# dcmctrl-mcu-board_v1.net
KiCad netlist of a schematic drawn in EAGLE
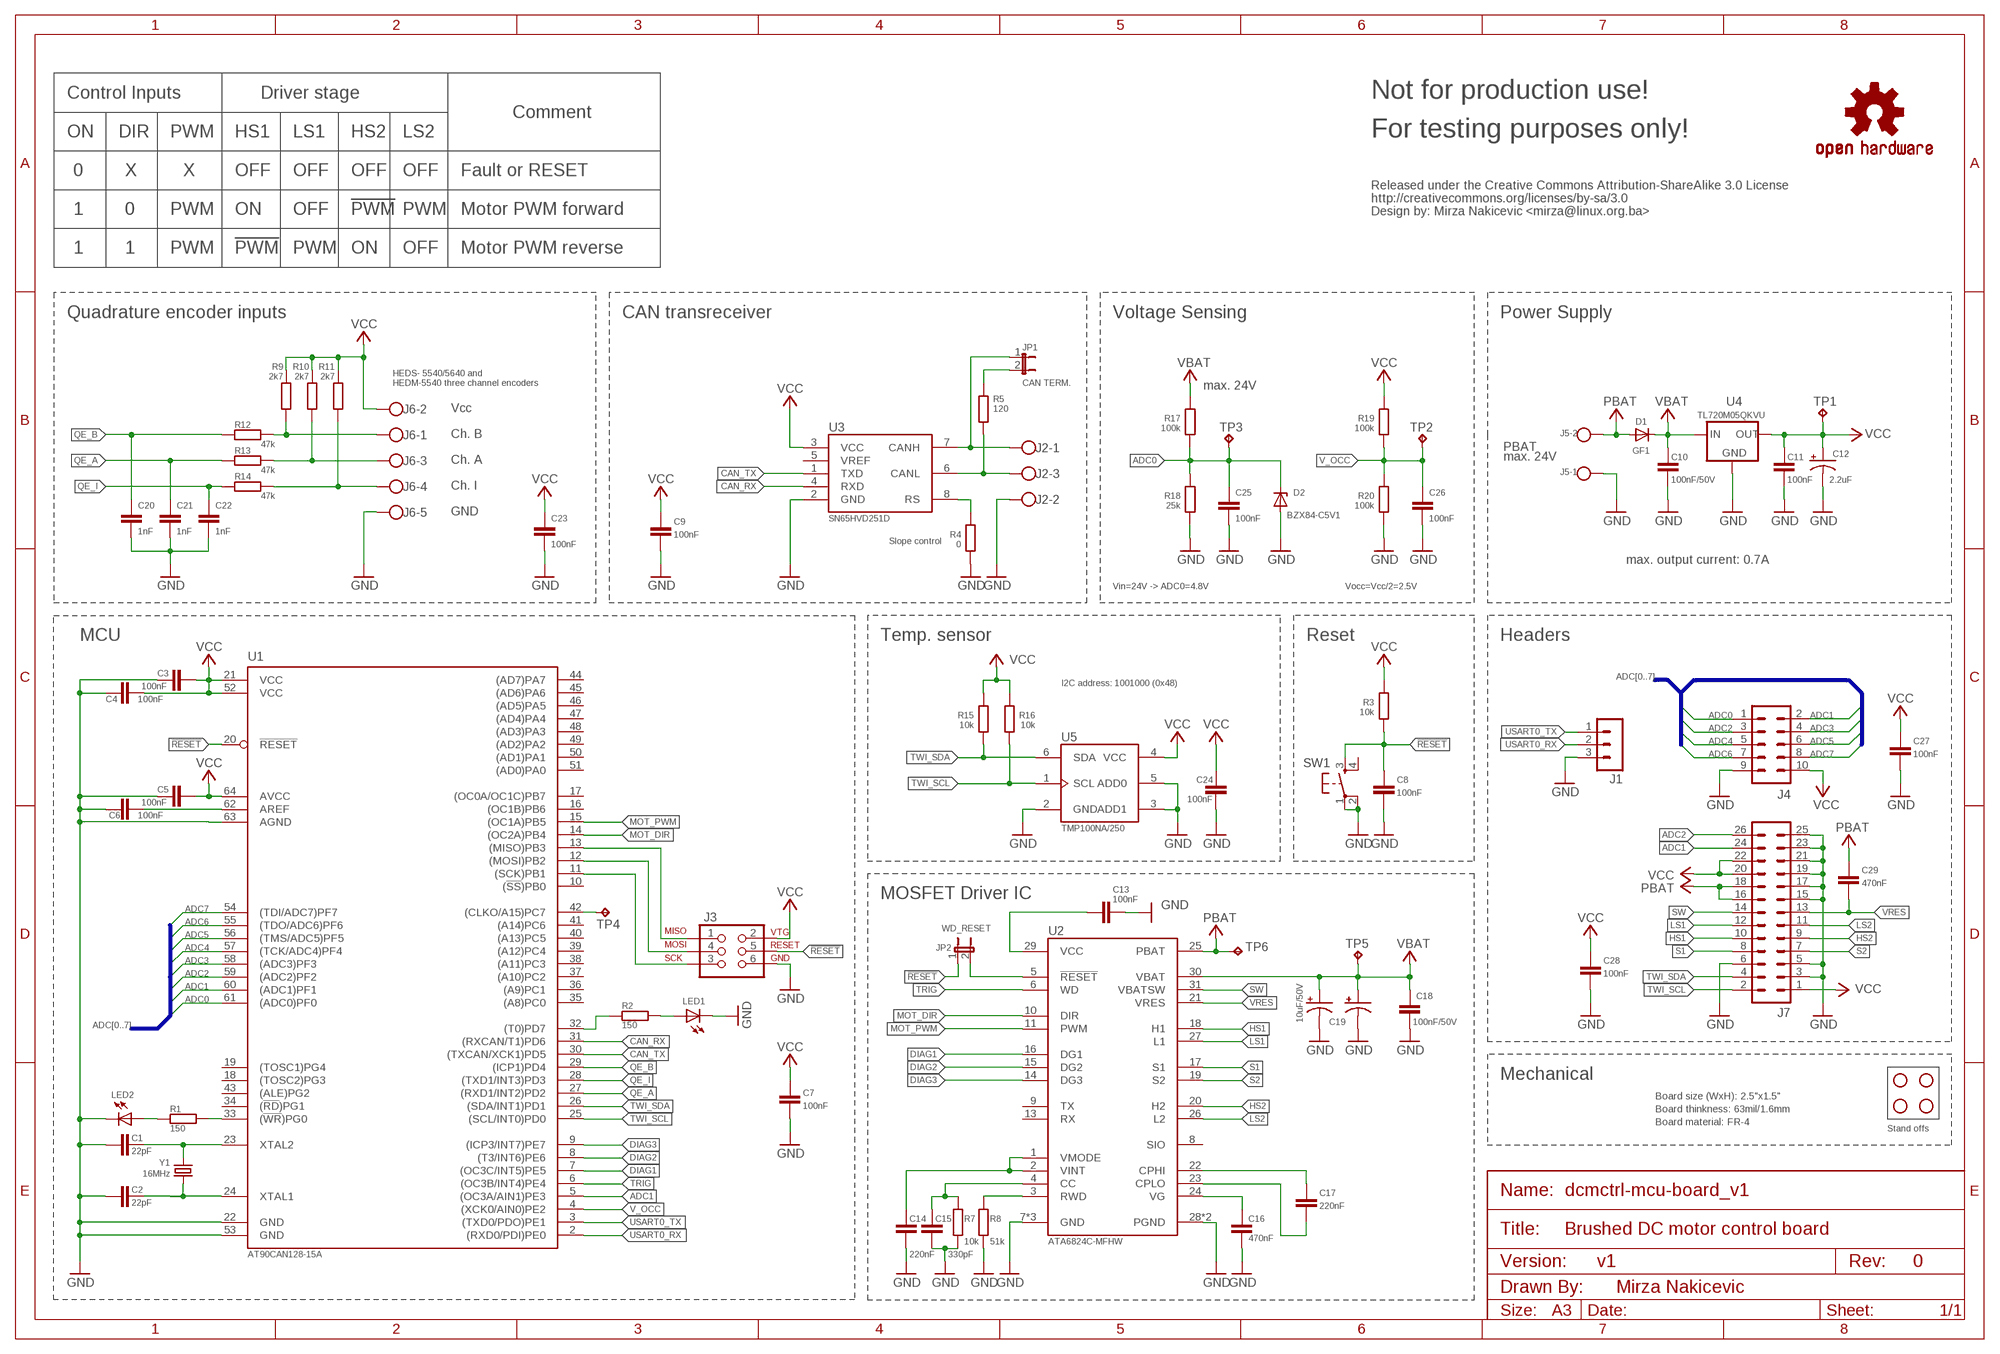
[diagram p0: schematic, sheet 1]

(export (version "E")
  (design (tool "Eeschema 10.0.6"))
  (components
    (comp (ref "C1")
      (value "22pF")
      (footprint "eagle-import:C0603")
      (libsource (lib "eagle-import") (part "C-0603"))
    )
    (comp (ref "C2")
      (value "22pF")
      (footprint "eagle-import:C0603")
      (libsource (lib "eagle-import") (part "C-0603"))
    )
    (comp (ref "C3")
      (value "100nF")
      (footprint "eagle-import:C0603")
      (libsource (lib "eagle-import") (part "C-0603"))
    )
    (comp (ref "C4")
      (value "100nF")
      (footprint "eagle-import:C0603")
      (libsource (lib "eagle-import") (part "C-0603"))
    )
    (comp (ref "C5")
      (value "100nF")
      (footprint "eagle-import:C0603")
      (libsource (lib "eagle-import") (part "C-0603"))
    )
    (comp (ref "C6")
      (value "100nF")
      (footprint "eagle-import:C0603")
      (libsource (lib "eagle-import") (part "C-0603"))
    )
    (comp (ref "C7")
      (value "100nF")
      (footprint "eagle-import:C0603")
      (libsource (lib "eagle-import") (part "C-0603"))
    )
    (comp (ref "C8")
      (value "100nF")
      (footprint "eagle-import:C0603")
      (libsource (lib "eagle-import") (part "C-0603"))
    )
    (comp (ref "C9")
      (value "100nF")
      (footprint "eagle-import:C0603")
      (libsource (lib "eagle-import") (part "C-0603"))
    )
    (comp (ref "C10")
      (value "100nF/50V")
      (footprint "eagle-import:C0603")
      (libsource (lib "eagle-import") (part "C-0603"))
    )
    (comp (ref "C11")
      (value "100nF")
      (footprint "eagle-import:C0603")
      (libsource (lib "eagle-import") (part "C-0603"))
    )
    (comp (ref "C12")
      (value "2.2uF")
      (footprint "eagle-import:EIA3216")
      (libsource (lib "eagle-import") (part "CPOL-1206"))
    )
    (comp (ref "C13")
      (value "100nF")
      (footprint "eagle-import:C0603")
      (libsource (lib "eagle-import") (part "C-0603"))
    )
    (comp (ref "C14")
      (value "220nF")
      (footprint "eagle-import:C0603")
      (libsource (lib "eagle-import") (part "C-0603"))
    )
    (comp (ref "C15")
      (value "330pF")
      (footprint "eagle-import:C0603")
      (libsource (lib "eagle-import") (part "C-0603"))
    )
    (comp (ref "C16")
      (value "470nF")
      (footprint "eagle-import:C0603")
      (libsource (lib "eagle-import") (part "C-0603"))
    )
    (comp (ref "C17")
      (value "220nF")
      (footprint "eagle-import:C0603")
      (libsource (lib "eagle-import") (part "C-0603"))
    )
    (comp (ref "C18")
      (value "100nF/50V")
      (footprint "eagle-import:C0603")
      (libsource (lib "eagle-import") (part "C-0603"))
    )
    (comp (ref "C19")
      (value "10uF/50V")
      (footprint "eagle-import:EIA3528")
      (libsource (lib "eagle-import") (part "CPOL-3528"))
    )
    (comp (ref "C20")
      (value "1nF")
      (footprint "eagle-import:C0603")
      (libsource (lib "eagle-import") (part "C-0603"))
    )
    (comp (ref "C21")
      (value "1nF")
      (footprint "eagle-import:C0603")
      (libsource (lib "eagle-import") (part "C-0603"))
    )
    (comp (ref "C22")
      (value "1nF")
      (footprint "eagle-import:C0603")
      (libsource (lib "eagle-import") (part "C-0603"))
    )
    (comp (ref "C23")
      (value "100nF")
      (footprint "eagle-import:C0603")
      (libsource (lib "eagle-import") (part "C-0603"))
    )
    (comp (ref "C24")
      (value "100nF")
      (footprint "eagle-import:C0603")
      (libsource (lib "eagle-import") (part "C-0603"))
    )
    (comp (ref "C25")
      (value "100nF")
      (footprint "eagle-import:C0603")
      (libsource (lib "eagle-import") (part "C-0603"))
    )
    (comp (ref "C26")
      (value "100nF")
      (footprint "eagle-import:C0603")
      (libsource (lib "eagle-import") (part "C-0603"))
    )
    (comp (ref "C27")
      (value "100nF")
      (footprint "eagle-import:C0603")
      (libsource (lib "eagle-import") (part "C-0603"))
    )
    (comp (ref "C28")
      (value "100nF")
      (footprint "eagle-import:C0603")
      (libsource (lib "eagle-import") (part "C-0603"))
    )
    (comp (ref "C29")
      (value "470nF")
      (footprint "eagle-import:C0603")
      (libsource (lib "eagle-import") (part "C-0603"))
    )
    (comp (ref "C999")
      (value "10uF/50V")
      (footprint "eagle-import:RADIAL-1")
      (libsource (lib "eagle-import") (part "CPOL-PTH-2"))
    )
    (comp (ref "D1")
      (value "GF1")
      (footprint "eagle-import:SMA-DO214AC")
      (libsource (lib "eagle-import") (part "GF1"))
    )
    (comp (ref "D2")
      (value "BZX84-C5V1")
      (footprint "eagle-import:TO236")
      (libsource (lib "eagle-import") (part "ZENER-DIODETO236"))
    )
    (comp (ref "J1")
      (value "MA03-1")
      (footprint "eagle-import:MA03-1")
      (libsource (lib "eagle-import") (part "MA03-1"))
    )
    (comp (ref "J2")
      (value "BLOCK3-3.5-4UCON")
      (footprint "eagle-import:4UCON-20193")
      (libsource (lib "eagle-import") (part "BLOCK3-3.5-4UCON"))
    )
    (comp (ref "J3")
      (value "AVR-ISP-6-100")
      (footprint "eagle-import:2X3-100")
      (libsource (lib "eagle-import") (part "AVR-ISP-6-100"))
    )
    (comp (ref "J4")
      (value "MA05-2")
      (footprint "eagle-import:MA05-2")
      (libsource (lib "eagle-import") (part "MA05-2"))
    )
    (comp (ref "J5")
      (value "BLOCK2-3.5-4UCON")
      (footprint "eagle-import:4UCON-19963")
      (libsource (lib "eagle-import") (part "BLOCK2-3.5-4UCON"))
    )
    (comp (ref "J6")
      (value "BLOCK5-3.5-4UCON")
      (footprint "eagle-import:4UCON-20223")
      (libsource (lib "eagle-import") (part "BLOCK5-3.5-4UCON"))
    )
    (comp (ref "J7")
      (value "MA13-2")
      (footprint "eagle-import:MA13-2")
      (libsource (lib "eagle-import") (part "MA13-2"))
    )
    (comp (ref "JP1")
      (value "JUMPER-2PTH")
      (footprint "eagle-import:1X02")
      (libsource (lib "eagle-import") (part "JUMPER-2PTH"))
    )
    (comp (ref "JP2")
      (value "JUMPER-2SMD-NC")
      (footprint "eagle-import:SJ_2S")
      (libsource (lib "eagle-import") (part "JUMPER-2SMD-NC"))
    )
    (comp (ref "LED1")
      (value "LEDCHIPLED_0603")
      (footprint "eagle-import:CHIPLED_0603")
      (libsource (lib "eagle-import") (part "LEDCHIPLED_0603"))
    )
    (comp (ref "LED2")
      (value "LEDCHIPLED_0603")
      (footprint "eagle-import:CHIPLED_0603")
      (libsource (lib "eagle-import") (part "LEDCHIPLED_0603"))
    )
    (comp (ref "R1")
      (value "150")
      (footprint "eagle-import:R0603")
      (libsource (lib "eagle-import") (part "R-0603"))
    )
    (comp (ref "R2")
      (value "150")
      (footprint "eagle-import:R0603")
      (libsource (lib "eagle-import") (part "R-0603"))
    )
    (comp (ref "R3")
      (value "10k")
      (footprint "eagle-import:R0603")
      (libsource (lib "eagle-import") (part "R-0603"))
    )
    (comp (ref "R4")
      (value "0")
      (footprint "eagle-import:R0603")
      (libsource (lib "eagle-import") (part "R-0603"))
    )
    (comp (ref "R5")
      (value "120")
      (footprint "eagle-import:R0805")
      (libsource (lib "eagle-import") (part "R-0805"))
    )
    (comp (ref "R7")
      (value "10k")
      (footprint "eagle-import:R0603")
      (libsource (lib "eagle-import") (part "R-0603"))
    )
    (comp (ref "R8")
      (value "51k")
      (footprint "eagle-import:R0603")
      (libsource (lib "eagle-import") (part "R-0603"))
    )
    (comp (ref "R9")
      (value "2k7")
      (footprint "eagle-import:R0603")
      (libsource (lib "eagle-import") (part "R-0603"))
    )
    (comp (ref "R10")
      (value "2k7")
      (footprint "eagle-import:R0603")
      (libsource (lib "eagle-import") (part "R-0603"))
    )
    (comp (ref "R11")
      (value "2k7")
      (footprint "eagle-import:R0603")
      (libsource (lib "eagle-import") (part "R-0603"))
    )
    (comp (ref "R12")
      (value "47k")
      (footprint "eagle-import:R0603")
      (libsource (lib "eagle-import") (part "R-0603"))
    )
    (comp (ref "R13")
      (value "47k")
      (footprint "eagle-import:R0603")
      (libsource (lib "eagle-import") (part "R-0603"))
    )
    (comp (ref "R14")
      (value "47k")
      (footprint "eagle-import:R0603")
      (libsource (lib "eagle-import") (part "R-0603"))
    )
    (comp (ref "R15")
      (value "10k")
      (footprint "eagle-import:R0603")
      (libsource (lib "eagle-import") (part "R-0603"))
    )
    (comp (ref "R16")
      (value "10k")
      (footprint "eagle-import:R0603")
      (libsource (lib "eagle-import") (part "R-0603"))
    )
    (comp (ref "R17")
      (value "100k")
      (footprint "eagle-import:R0603")
      (libsource (lib "eagle-import") (part "R-0603"))
    )
    (comp (ref "R18")
      (value "25k")
      (footprint "eagle-import:R0603")
      (libsource (lib "eagle-import") (part "R-0603"))
    )
    (comp (ref "R19")
      (value "100k")
      (footprint "eagle-import:R0603")
      (libsource (lib "eagle-import") (part "R-0603"))
    )
    (comp (ref "R20")
      (value "100k")
      (footprint "eagle-import:R0603")
      (libsource (lib "eagle-import") (part "R-0603"))
    )
    (comp (ref "SW1")
      (value "TAC_SWITCHPTH")
      (footprint "eagle-import:TACTILE-PTH")
      (libsource (lib "eagle-import") (part "TAC_SWITCHPTH"))
    )
    (comp (ref "TP1")
      (value "TPB1,27")
      (footprint "eagle-import:B1,27")
      (libsource (lib "eagle-import") (part "TPB1,27"))
    )
    (comp (ref "TP2")
      (value "TPB1,27")
      (footprint "eagle-import:B1,27")
      (libsource (lib "eagle-import") (part "TPB1,27"))
    )
    (comp (ref "TP3")
      (value "TPB1,27")
      (footprint "eagle-import:B1,27")
      (libsource (lib "eagle-import") (part "TPB1,27"))
    )
    (comp (ref "TP4")
      (value "TPB1,27")
      (footprint "eagle-import:B1,27")
      (libsource (lib "eagle-import") (part "TPB1,27"))
    )
    (comp (ref "TP5")
      (value "TPB1,27")
      (footprint "eagle-import:B1,27")
      (libsource (lib "eagle-import") (part "TPB1,27"))
    )
    (comp (ref "TP6")
      (value "TPB1,27")
      (footprint "eagle-import:B1,27")
      (libsource (lib "eagle-import") (part "TPB1,27"))
    )
    (comp (ref "U$1")
      (value "STAND-OFF")
      (footprint "eagle-import:STAND-OFF")
      (libsource (lib "eagle-import") (part "STAND-OFF"))
    )
    (comp (ref "U$2")
      (value "STAND-OFF")
      (footprint "eagle-import:STAND-OFF")
      (libsource (lib "eagle-import") (part "STAND-OFF"))
    )
    (comp (ref "U$3")
      (value "STAND-OFF")
      (footprint "eagle-import:STAND-OFF")
      (libsource (lib "eagle-import") (part "STAND-OFF"))
    )
    (comp (ref "U$4")
      (value "STAND-OFF")
      (footprint "eagle-import:STAND-OFF")
      (libsource (lib "eagle-import") (part "STAND-OFF"))
    )
    (comp (ref "U$24")
      (value "OSHW-LOGOM")
      (footprint "eagle-import:OSHW-LOGO-M")
      (libsource (lib "eagle-import") (part "OSHW-LOGOM"))
    )
    (comp (ref "U$29")
      (value "CC-SA")
      (footprint "eagle-import:CC-SA")
      (libsource (lib "eagle-import") (part "CC-SA"))
    )
    (comp (ref "U1")
      (value "AT90CAN128-15A")
      (footprint "eagle-import:TQFP64")
      (libsource (lib "eagle-import") (part "AT90CAN-15A128"))
    )
    (comp (ref "U2")
      (value "ATA6824C-MFHW")
      (footprint "eagle-import:TPQFP32")
      (libsource (lib "eagle-import") (part "ATA6824C-MFHW"))
    )
    (comp (ref "U3")
      (value "SN65HVD251D")
      (footprint "eagle-import:SO-08")
      (libsource (lib "eagle-import") (part "SN65HVD251D"))
    )
    (comp (ref "U4")
      (value "TL720M05QKVU")
      (footprint "eagle-import:D-PAK_TO252AA")
      (libsource (lib "eagle-import") (part "TL720M05QKVU"))
    )
    (comp (ref "U5")
      (value "TMP100NA/250")
      (footprint "eagle-import:SOT23-6L")
      (libsource (lib "eagle-import") (part "TMP100NA/250"))
    )
    (comp (ref "Y1")
      (value "16MHz")
      (footprint "eagle-import:HC49U-V")
      (libsource (lib "eagle-import") (part "CRYSTAL-HC49UV"))
    )
  )
  (nets
    (net (code "1") (name "/ADC3") (class "Default")
      (node (ref "J4") (pin "4") (pinfunction "4_4") (pintype "passive"))
      (node (ref "U1") (pin "58") (pinfunction "(ADC3)PF3_58") (pintype "bidirectional"))
    )
    (net (code "2") (name "/ADC4") (class "Default")
      (node (ref "J4") (pin "5") (pinfunction "5_5") (pintype "passive"))
      (node (ref "U1") (pin "57") (pinfunction "(TCK/ADC4)PF4_57") (pintype "bidirectional"))
    )
    (net (code "3") (name "/ADC5") (class "Default")
      (node (ref "J4") (pin "6") (pinfunction "6_6") (pintype "passive"))
      (node (ref "U1") (pin "56") (pinfunction "(TMS/ADC5)PF5_56") (pintype "bidirectional"))
    )
    (net (code "4") (name "/ADC6") (class "Default")
      (node (ref "J4") (pin "7") (pinfunction "7_7") (pintype "passive"))
      (node (ref "U1") (pin "55") (pinfunction "(TDO/ADC6)PF6_55") (pintype "bidirectional"))
    )
    (net (code "5") (name "/ADC7") (class "Default")
      (node (ref "J4") (pin "8") (pinfunction "8_8") (pintype "passive"))
      (node (ref "U1") (pin "54") (pinfunction "(TDI/ADC7)PF7_54") (pintype "bidirectional"))
    )
    (net (code "7") (name "/~{RESET}") (class "Default")
      (node (ref "C8") (pin "1") (pinfunction "1_1") (pintype "passive"))
      (node (ref "J3") (pin "5") (pinfunction "5_5") (pintype "passive"))
      (node (ref "JP2") (pin "1") (pinfunction "1_1") (pintype "passive"))
      (node (ref "R3") (pin "1") (pinfunction "1_1") (pintype "passive"))
      (node (ref "SW1") (pin "3") (pinfunction "3_3") (pintype "passive"))
      (node (ref "U1") (pin "20") (pinfunction "~{RESET}_20") (pintype "input"))
    )
    (net (code "8") (name "ADC0") (class "Default")
      (node (ref "C25") (pin "1") (pinfunction "1_1") (pintype "passive"))
      (node (ref "D2") (pin "C") (pinfunction "C_C") (pintype "passive"))
      (node (ref "J4") (pin "1") (pinfunction "1_1") (pintype "passive"))
      (node (ref "R17") (pin "1") (pinfunction "1_1") (pintype "passive"))
      (node (ref "R18") (pin "2") (pinfunction "2_2") (pintype "passive"))
      (node (ref "TP3") (pin "TP") (pinfunction "TP_TP") (pintype "input"))
      (node (ref "U1") (pin "61") (pinfunction "(ADC0)PF0_61") (pintype "bidirectional"))
    )
    (net (code "9") (name "ADC1") (class "Default")
      (node (ref "J4") (pin "2") (pinfunction "2_2") (pintype "passive"))
      (node (ref "J7") (pin "24") (pinfunction "24_24") (pintype "passive"))
      (node (ref "U1") (pin "5") (pinfunction "(OC3A/AIN1)PE3_5") (pintype "bidirectional"))
      (node (ref "U1") (pin "60") (pinfunction "(ADC1)PF1_60") (pintype "bidirectional"))
    )
    (net (code "10") (name "ADC2") (class "Default")
      (node (ref "J4") (pin "3") (pinfunction "3_3") (pintype "passive"))
      (node (ref "J7") (pin "26") (pinfunction "26_26") (pintype "passive"))
      (node (ref "U1") (pin "59") (pinfunction "(ADC2)PF2_59") (pintype "bidirectional"))
    )
    (net (code "11") (name "CAN_RX") (class "Default")
      (node (ref "U1") (pin "31") (pinfunction "(RXCAN/T1)PD6_31") (pintype "bidirectional"))
      (node (ref "U3") (pin "4") (pinfunction "RXD_4") (pintype "bidirectional"))
    )
    (net (code "12") (name "CAN_TX") (class "Default")
      (node (ref "U1") (pin "30") (pinfunction "(TXCAN/XCK1)PD5_30") (pintype "bidirectional"))
      (node (ref "U3") (pin "1") (pinfunction "TXD_1") (pintype "output"))
    )
    (net (code "13") (name "DIAG1") (class "Default")
      (node (ref "U1") (pin "7") (pinfunction "(OC3C/INT5)PE5_7") (pintype "bidirectional"))
      (node (ref "U2") (pin "16") (pinfunction "DG1_16") (pintype "output"))
    )
    (net (code "14") (name "DIAG2") (class "Default")
      (node (ref "U1") (pin "8") (pinfunction "(T3/INT6)PE6_8") (pintype "bidirectional"))
      (node (ref "U2") (pin "15") (pinfunction "DG2_15") (pintype "output"))
    )
    (net (code "15") (name "DIAG3") (class "Default")
      (node (ref "U1") (pin "9") (pinfunction "(ICP3/INT7)PE7_9") (pintype "bidirectional"))
      (node (ref "U2") (pin "14") (pinfunction "DG3_14") (pintype "output"))
    )
    (net (code "16") (name "GND") (class "Default")
      (node (ref "C1") (pin "2") (pinfunction "2_2") (pintype "passive"))
      (node (ref "C10") (pin "2") (pinfunction "2_2") (pintype "passive"))
      (node (ref "C11") (pin "2") (pinfunction "2_2") (pintype "passive"))
      (node (ref "C12") (pin "C") (pinfunction "-_C") (pintype "passive"))
      (node (ref "C13") (pin "2") (pinfunction "2_2") (pintype "passive"))
      (node (ref "C14") (pin "2") (pinfunction "2_2") (pintype "passive"))
      (node (ref "C15") (pin "2") (pinfunction "2_2") (pintype "passive"))
      (node (ref "C16") (pin "2") (pinfunction "2_2") (pintype "passive"))
      (node (ref "C18") (pin "2") (pinfunction "2_2") (pintype "passive"))
      (node (ref "C19") (pin "C") (pinfunction "-_C") (pintype "passive"))
      (node (ref "C2") (pin "2") (pinfunction "2_2") (pintype "passive"))
      (node (ref "C20") (pin "2") (pinfunction "2_2") (pintype "passive"))
      (node (ref "C21") (pin "2") (pinfunction "2_2") (pintype "passive"))
      (node (ref "C22") (pin "2") (pinfunction "2_2") (pintype "passive"))
      (node (ref "C23") (pin "2") (pinfunction "2_2") (pintype "passive"))
      (node (ref "C24") (pin "2") (pinfunction "2_2") (pintype "passive"))
      (node (ref "C25") (pin "2") (pinfunction "2_2") (pintype "passive"))
      (node (ref "C26") (pin "2") (pinfunction "2_2") (pintype "passive"))
      (node (ref "C27") (pin "2") (pinfunction "2_2") (pintype "passive"))
      (node (ref "C28") (pin "2") (pinfunction "2_2") (pintype "passive"))
      (node (ref "C3") (pin "2") (pinfunction "2_2") (pintype "passive"))
      (node (ref "C4") (pin "2") (pinfunction "2_2") (pintype "passive"))
      (node (ref "C5") (pin "2") (pinfunction "2_2") (pintype "passive"))
      (node (ref "C6") (pin "2") (pinfunction "2_2") (pintype "passive"))
      (node (ref "C7") (pin "2") (pinfunction "2_2") (pintype "passive"))
      (node (ref "C8") (pin "2") (pinfunction "2_2") (pintype "passive"))
      (node (ref "C9") (pin "2") (pinfunction "2_2") (pintype "passive"))
      (node (ref "C999") (pin "2") (pinfunction "-_2") (pintype "passive"))
      (node (ref "D2") (pin "A") (pinfunction "A_A") (pintype "passive"))
      (node (ref "J1") (pin "3") (pinfunction "3_3") (pintype "passive"))
      (node (ref "J2") (pin "2") (pinfunction "KL_2") (pintype "passive"))
      (node (ref "J3") (pin "6") (pinfunction "6_6") (pintype "passive"))
      (node (ref "J4") (pin "9") (pinfunction "9_9") (pintype "passive"))
      (node (ref "J5") (pin "1") (pinfunction "KL_1") (pintype "passive"))
      (node (ref "J6") (pin "5") (pinfunction "KL_5") (pintype "passive"))
      (node (ref "J7") (pin "15") (pinfunction "15_15") (pintype "passive"))
      (node (ref "J7") (pin "17") (pinfunction "17_17") (pintype "passive"))
      (node (ref "J7") (pin "19") (pinfunction "19_19") (pintype "passive"))
      (node (ref "J7") (pin "21") (pinfunction "21_21") (pintype "passive"))
      (node (ref "J7") (pin "23") (pinfunction "23_23") (pintype "passive"))
      (node (ref "J7") (pin "25") (pinfunction "25_25") (pintype "passive"))
      (node (ref "J7") (pin "3") (pinfunction "3_3") (pintype "passive"))
      (node (ref "J7") (pin "5") (pinfunction "5_5") (pintype "passive"))
      (node (ref "J7") (pin "6") (pinfunction "6_6") (pintype "passive"))
      (node (ref "LED1") (pin "C") (pinfunction "C_C") (pintype "passive"))
      (node (ref "LED2") (pin "C") (pinfunction "C_C") (pintype "passive"))
      (node (ref "R18") (pin "1") (pinfunction "1_1") (pintype "passive"))
      (node (ref "R20") (pin "1") (pinfunction "1_1") (pintype "passive"))
      (node (ref "R4") (pin "1") (pinfunction "1_1") (pintype "passive"))
      (node (ref "R7") (pin "1") (pinfunction "1_1") (pintype "passive"))
      (node (ref "R8") (pin "1") (pinfunction "1_1") (pintype "passive"))
      (node (ref "SW1") (pin "1") (pinfunction "1_1") (pintype "passive"))
      (node (ref "SW1") (pin "2") (pinfunction "2_2") (pintype "passive"))
      (node (ref "U1") (pin "22") (pinfunction "GND_22") (pintype "power_in"))
      (node (ref "U1") (pin "53") (pinfunction "GND_53") (pintype "power_in"))
      (node (ref "U1") (pin "63") (pinfunction "AGND_63") (pintype "power_in"))
      (node (ref "U2") (pin "12") (pinfunction "GND_12") (pintype "power_in"))
      (node (ref "U2") (pin "28") (pinfunction "PGND_28") (pintype "input"))
      (node (ref "U2") (pin "32") (pinfunction "GND_32") (pintype "power_in"))
      (node (ref "U2") (pin "33") (pinfunction "PGND_33") (pintype "input"))
      (node (ref "U2") (pin "7") (pinfunction "GND_7") (pintype "power_in"))
      (node (ref "U3") (pin "2") (pinfunction "GND_2") (pintype "power_in"))
      (node (ref "U4") (pin "4") (pinfunction "GND_4") (pintype "power_in"))
      (node (ref "U5") (pin "2") (pinfunction "GND_2") (pintype "power_in"))
      (node (ref "U5") (pin "3") (pinfunction "ADD1_3") (pintype "input"))
      (node (ref "U5") (pin "5") (pinfunction "ADD0_5") (pintype "input"))
    )
    (net (code "17") (name "HS1") (class "Default")
      (node (ref "J7") (pin "10") (pinfunction "10_10") (pintype "passive"))
      (node (ref "U2") (pin "18") (pinfunction "H1_18") (pintype "output"))
    )
    (net (code "18") (name "HS2") (class "Default")
      (node (ref "J7") (pin "9") (pinfunction "9_9") (pintype "passive"))
      (node (ref "U2") (pin "20") (pinfunction "H2_20") (pintype "output"))
    )
    (net (code "19") (name "LS1") (class "Default")
      (node (ref "J7") (pin "12") (pinfunction "12_12") (pintype "passive"))
      (node (ref "U2") (pin "27") (pinfunction "L1_27") (pintype "output"))
    )
    (net (code "20") (name "LS2") (class "Default")
      (node (ref "J7") (pin "11") (pinfunction "11_11") (pintype "passive"))
      (node (ref "U2") (pin "26") (pinfunction "L2_26") (pintype "output"))
    )
    (net (code "21") (name "MOT_DIR") (class "Default")
      (node (ref "U1") (pin "14") (pinfunction "(OC2A)PB4_14") (pintype "bidirectional"))
      (node (ref "U2") (pin "10") (pinfunction "DIR_10") (pintype "input"))
    )
    (net (code "22") (name "MOT_PWM") (class "Default")
      (node (ref "U1") (pin "15") (pinfunction "(OC1A)PB5_15") (pintype "bidirectional"))
      (node (ref "U2") (pin "11") (pinfunction "PWM_11") (pintype "input"))
    )
    (net (code "23") (name "Net-(J2A-KL)") (class "Default")
      (node (ref "J2") (pin "1") (pinfunction "KL_1") (pintype "passive"))
      (node (ref "JP1") (pin "1") (pinfunction "1_1") (pintype "passive"))
      (node (ref "U3") (pin "7") (pinfunction "CANH_7") (pintype "bidirectional"))
    )
    (net (code "24") (name "Net-(J2C-KL)") (class "Default")
      (node (ref "J2") (pin "3") (pinfunction "KL_3") (pintype "passive"))
      (node (ref "R5") (pin "2") (pinfunction "2_2") (pintype "passive"))
      (node (ref "U3") (pin "6") (pinfunction "CANL_6") (pintype "bidirectional"))
    )
    (net (code "25") (name "Net-(J6A-KL)") (class "Default")
      (node (ref "J6") (pin "1") (pinfunction "KL_1") (pintype "passive"))
      (node (ref "R12") (pin "2") (pinfunction "2_2") (pintype "passive"))
      (node (ref "R9") (pin "1") (pinfunction "1_1") (pintype "passive"))
    )
    (net (code "26") (name "Net-(J6C-KL)") (class "Default")
      (node (ref "J6") (pin "3") (pinfunction "KL_3") (pintype "passive"))
      (node (ref "R10") (pin "1") (pinfunction "1_1") (pintype "passive"))
      (node (ref "R13") (pin "2") (pinfunction "2_2") (pintype "passive"))
    )
    (net (code "27") (name "Net-(J6D-KL)") (class "Default")
      (node (ref "J6") (pin "4") (pinfunction "KL_4") (pintype "passive"))
      (node (ref "R11") (pin "1") (pinfunction "1_1") (pintype "passive"))
      (node (ref "R14") (pin "2") (pinfunction "2_2") (pintype "passive"))
    )
    (net (code "28") (name "Net-(JP1-Pad2)") (class "Default")
      (node (ref "JP1") (pin "2") (pinfunction "2_2") (pintype "passive"))
      (node (ref "R5") (pin "1") (pinfunction "1_1") (pintype "passive"))
    )
    (net (code "29") (name "Net-(LED1-PadA)") (class "Default")
      (node (ref "LED1") (pin "A") (pinfunction "A_A") (pintype "passive"))
      (node (ref "R2") (pin "1") (pinfunction "1_1") (pintype "passive"))
    )
    (net (code "30") (name "Net-(LED2-PadA)") (class "Default")
      (node (ref "LED2") (pin "A") (pinfunction "A_A") (pintype "passive"))
      (node (ref "R1") (pin "1") (pinfunction "1_1") (pintype "passive"))
    )
    (net (code "31") (name "Net-(U1-(CLKO{slash}A15)PC7)") (class "Default")
      (node (ref "TP4") (pin "TP") (pinfunction "TP_TP") (pintype "input"))
      (node (ref "U1") (pin "42") (pinfunction "(CLKO/A15)PC7_42") (pintype "bidirectional"))
    )
    (net (code "32") (name "Net-(U1-(MISO)PB3)") (class "Default")
      (node (ref "J3") (pin "1") (pinfunction "1_1") (pintype "passive"))
      (node (ref "U1") (pin "13") (pinfunction "(MISO)PB3_13") (pintype "bidirectional"))
    )
    (net (code "33") (name "Net-(U1-(MOSI)PB2)") (class "Default")
      (node (ref "J3") (pin "4") (pinfunction "4_4") (pintype "passive"))
      (node (ref "U1") (pin "12") (pinfunction "(MOSI)PB2_12") (pintype "bidirectional"))
    )
    (net (code "34") (name "Net-(U1-(SCK)PB1)") (class "Default")
      (node (ref "J3") (pin "3") (pinfunction "3_3") (pintype "passive"))
      (node (ref "U1") (pin "11") (pinfunction "(SCK)PB1_11") (pintype "bidirectional"))
    )
    (net (code "35") (name "Net-(U1-(T0)PD7)") (class "Default")
      (node (ref "R2") (pin "2") (pinfunction "2_2") (pintype "passive"))
      (node (ref "U1") (pin "32") (pinfunction "(T0)PD7_32") (pintype "bidirectional"))
    )
    (net (code "36") (name "Net-(U1-(~{WR})PG0)") (class "Default")
      (node (ref "R1") (pin "2") (pinfunction "2_2") (pintype "passive"))
      (node (ref "U1") (pin "33") (pinfunction "(~{WR})PG0_33") (pintype "bidirectional"))
    )
    (net (code "37") (name "Net-(U1-AREF)") (class "Default")
      (node (ref "C6") (pin "1") (pinfunction "1_1") (pintype "passive"))
      (node (ref "U1") (pin "62") (pinfunction "AREF_62") (pintype "bidirectional"))
    )
    (net (code "38") (name "Net-(U1-XTAL1)") (class "Default")
      (node (ref "C2") (pin "1") (pinfunction "1_1") (pintype "passive"))
      (node (ref "U1") (pin "24") (pinfunction "XTAL1_24") (pintype "input"))
      (node (ref "Y1") (pin "2") (pinfunction "2_2") (pintype "passive"))
    )
    (net (code "39") (name "Net-(U1-XTAL2)") (class "Default")
      (node (ref "C1") (pin "1") (pinfunction "1_1") (pintype "passive"))
      (node (ref "U1") (pin "23") (pinfunction "XTAL2_23") (pintype "output"))
      (node (ref "Y1") (pin "1") (pinfunction "1_1") (pintype "passive"))
    )
    (net (code "40") (name "Net-(U2-CC)") (class "Default")
      (node (ref "C15") (pin "1") (pinfunction "1_1") (pintype "passive"))
      (node (ref "R7") (pin "2") (pinfunction "2_2") (pintype "passive"))
      (node (ref "U2") (pin "4") (pinfunction "CC_4") (pintype "passive"))
    )
    (net (code "41") (name "Net-(U2-CPHI)") (class "Default")
      (node (ref "C17") (pin "1") (pinfunction "1_1") (pintype "passive"))
      (node (ref "U2") (pin "22") (pinfunction "CPHI_22") (pintype "passive"))
    )
    (net (code "42") (name "Net-(U2-CPLO)") (class "Default")
      (node (ref "C17") (pin "2") (pinfunction "2_2") (pintype "passive"))
      (node (ref "U2") (pin "23") (pinfunction "CPLO_23") (pintype "passive"))
    )
    (net (code "43") (name "Net-(U2-RWD)") (class "Default")
      (node (ref "R8") (pin "2") (pinfunction "2_2") (pintype "passive"))
      (node (ref "U2") (pin "3") (pinfunction "RWD_3") (pintype "passive"))
    )
    (net (code "44") (name "Net-(U2-VCC)") (class "Default")
      (node (ref "C13") (pin "1") (pinfunction "1_1") (pintype "passive"))
      (node (ref "U2") (pin "29") (pinfunction "VCC_29") (pintype "power_in"))
    )
    (net (code "45") (name "Net-(U2-VG)") (class "Default")
      (node (ref "C16") (pin "1") (pinfunction "1_1") (pintype "passive"))
      (node (ref "U2") (pin "24") (pinfunction "VG_24") (pintype "passive"))
    )
    (net (code "46") (name "Net-(U2-VINT)") (class "Default")
      (node (ref "C14") (pin "1") (pinfunction "1_1") (pintype "passive"))
      (node (ref "U2") (pin "1") (pinfunction "VMODE_1") (pintype "input"))
      (node (ref "U2") (pin "2") (pinfunction "VINT_2") (pintype "passive"))
    )
    (net (code "47") (name "Net-(U2-~{RESET})") (class "Default")
      (node (ref "JP2") (pin "2") (pinfunction "2_2") (pintype "passive"))
      (node (ref "U2") (pin "5") (pinfunction "~{RESET}_5") (pintype "output"))
    )
    (net (code "48") (name "Net-(U3-RS)") (class "Default")
      (node (ref "R4") (pin "2") (pinfunction "2_2") (pintype "passive"))
      (node (ref "U3") (pin "8") (pinfunction "RS_8") (pintype "passive"))
    )
    (net (code "49") (name "PBAT") (class "Default")
      (node (ref "C29") (pin "1") (pinfunction "1_1") (pintype "passive"))
      (node (ref "D1") (pin "A") (pinfunction "A_A") (pintype "passive"))
      (node (ref "J5") (pin "2") (pinfunction "KL_2") (pintype "passive"))
      (node (ref "J7") (pin "16") (pinfunction "16_16") (pintype "passive"))
      (node (ref "J7") (pin "18") (pinfunction "18_18") (pintype "passive"))
      (node (ref "TP6") (pin "TP") (pinfunction "TP_TP") (pintype "input"))
      (node (ref "U2") (pin "25") (pinfunction "PBAT_25") (pintype "input"))
    )
    (net (code "50") (name "QE_A") (class "Default")
      (node (ref "C21") (pin "1") (pinfunction "1_1") (pintype "passive"))
      (node (ref "R13") (pin "1") (pinfunction "1_1") (pintype "passive"))
      (node (ref "U1") (pin "27") (pinfunction "(RXD1/INT2)PD2_27") (pintype "bidirectional"))
    )
    (net (code "51") (name "QE_B") (class "Default")
      (node (ref "C20") (pin "1") (pinfunction "1_1") (pintype "passive"))
      (node (ref "R12") (pin "1") (pinfunction "1_1") (pintype "passive"))
      (node (ref "U1") (pin "29") (pinfunction "(ICP1)PD4_29") (pintype "bidirectional"))
    )
    (net (code "52") (name "QE_I") (class "Default")
      (node (ref "C22") (pin "1") (pinfunction "1_1") (pintype "passive"))
      (node (ref "R14") (pin "1") (pinfunction "1_1") (pintype "passive"))
      (node (ref "U1") (pin "28") (pinfunction "(TXD1/INT3)PD3_28") (pintype "bidirectional"))
    )
    (net (code "53") (name "S1") (class "Default")
      (node (ref "J7") (pin "8") (pinfunction "8_8") (pintype "passive"))
      (node (ref "U2") (pin "17") (pinfunction "S1_17") (pintype "bidirectional"))
    )
    (net (code "54") (name "S2") (class "Default")
      (node (ref "J7") (pin "7") (pinfunction "7_7") (pintype "passive"))
      (node (ref "U2") (pin "19") (pinfunction "S2_19") (pintype "bidirectional"))
    )
    (net (code "55") (name "SW") (class "Default")
      (node (ref "J7") (pin "14") (pinfunction "14_14") (pintype "passive"))
      (node (ref "U2") (pin "31") (pinfunction "VBATSW_31") (pintype "output"))
    )
    (net (code "56") (name "TRIG") (class "Default")
      (node (ref "U1") (pin "6") (pinfunction "(OC3B/INT4)PE4_6") (pintype "bidirectional"))
      (node (ref "U2") (pin "6") (pinfunction "WD_6") (pintype "input"))
    )
    (net (code "57") (name "TWI_SCL") (class "Default")
      (node (ref "J7") (pin "2") (pinfunction "2_2") (pintype "passive"))
      (node (ref "R16") (pin "1") (pinfunction "1_1") (pintype "passive"))
      (node (ref "U1") (pin "25") (pinfunction "(SCL/INT0)PD0_25") (pintype "bidirectional"))
      (node (ref "U5") (pin "1") (pinfunction "SCL_1") (pintype "input"))
    )
    (net (code "58") (name "TWI_SDA") (class "Default")
      (node (ref "J7") (pin "4") (pinfunction "4_4") (pintype "passive"))
      (node (ref "R15") (pin "1") (pinfunction "1_1") (pintype "passive"))
      (node (ref "U1") (pin "26") (pinfunction "(SDA/INT1)PD1_26") (pintype "bidirectional"))
      (node (ref "U5") (pin "6") (pinfunction "SDA_6") (pintype "bidirectional"))
    )
    (net (code "59") (name "USART0_RX") (class "Default")
      (node (ref "J1") (pin "2") (pinfunction "2_2") (pintype "passive"))
      (node (ref "U1") (pin "2") (pinfunction "(RXD0/PDI)PE0_2") (pintype "bidirectional"))
    )
    (net (code "60") (name "USART0_TX") (class "Default")
      (node (ref "J1") (pin "1") (pinfunction "1_1") (pintype "passive"))
      (node (ref "U1") (pin "3") (pinfunction "(TXD0/PDO)PE1_3") (pintype "bidirectional"))
    )
    (net (code "61") (name "VBAT") (class "Default")
      (node (ref "C10") (pin "1") (pinfunction "1_1") (pintype "passive"))
      (node (ref "C18") (pin "1") (pinfunction "1_1") (pintype "passive"))
      (node (ref "C19") (pin "A") (pinfunction "+_A") (pintype "passive"))
      (node (ref "C999") (pin "1") (pinfunction "+_1") (pintype "passive"))
      (node (ref "D1") (pin "K") (pinfunction "C_K") (pintype "passive"))
      (node (ref "R17") (pin "2") (pinfunction "2_2") (pintype "passive"))
      (node (ref "TP5") (pin "TP") (pinfunction "TP_TP") (pintype "input"))
      (node (ref "U2") (pin "30") (pinfunction "VBAT_30") (pintype "input"))
      (node (ref "U4") (pin "1") (pinfunction "IN_1") (pintype "input"))
    )
    (net (code "62") (name "VCC") (class "Default")
      (node (ref "C11") (pin "1") (pinfunction "1_1") (pintype "passive"))
      (node (ref "C12") (pin "A") (pinfunction "+_A") (pintype "passive"))
      (node (ref "C23") (pin "1") (pinfunction "1_1") (pintype "passive"))
      (node (ref "C24") (pin "1") (pinfunction "1_1") (pintype "passive"))
      (node (ref "C27") (pin "1") (pinfunction "1_1") (pintype "passive"))
      (node (ref "C28") (pin "1") (pinfunction "1_1") (pintype "passive"))
      (node (ref "C3") (pin "1") (pinfunction "1_1") (pintype "passive"))
      (node (ref "C4") (pin "1") (pinfunction "1_1") (pintype "passive"))
      (node (ref "C5") (pin "1") (pinfunction "1_1") (pintype "passive"))
      (node (ref "C7") (pin "1") (pinfunction "1_1") (pintype "passive"))
      (node (ref "C9") (pin "1") (pinfunction "1_1") (pintype "passive"))
      (node (ref "J3") (pin "2") (pinfunction "2_2") (pintype "passive"))
      (node (ref "J4") (pin "10") (pinfunction "10_10") (pintype "passive"))
      (node (ref "J6") (pin "2") (pinfunction "KL_2") (pintype "passive"))
      (node (ref "J7") (pin "1") (pinfunction "1_1") (pintype "passive"))
      (node (ref "J7") (pin "20") (pinfunction "20_20") (pintype "passive"))
      (node (ref "J7") (pin "22") (pinfunction "22_22") (pintype "passive"))
      (node (ref "R10") (pin "2") (pinfunction "2_2") (pintype "passive"))
      (node (ref "R11") (pin "2") (pinfunction "2_2") (pintype "passive"))
      (node (ref "R15") (pin "2") (pinfunction "2_2") (pintype "passive"))
      (node (ref "R16") (pin "2") (pinfunction "2_2") (pintype "passive"))
      (node (ref "R19") (pin "2") (pinfunction "2_2") (pintype "passive"))
      (node (ref "R3") (pin "2") (pinfunction "2_2") (pintype "passive"))
      (node (ref "R9") (pin "2") (pinfunction "2_2") (pintype "passive"))
      (node (ref "TP1") (pin "TP") (pinfunction "TP_TP") (pintype "input"))
      (node (ref "U1") (pin "21") (pinfunction "VCC_21") (pintype "power_in"))
      (node (ref "U1") (pin "52") (pinfunction "VCC_52") (pintype "power_in"))
      (node (ref "U1") (pin "64") (pinfunction "AVCC_64") (pintype "power_in"))
      (node (ref "U3") (pin "3") (pinfunction "VCC_3") (pintype "power_in"))
      (node (ref "U4") (pin "3") (pinfunction "OUT_3") (pintype "output"))
      (node (ref "U5") (pin "4") (pinfunction "VCC_4") (pintype "power_in"))
    )
    (net (code "63") (name "VRES") (class "Default")
      (node (ref "C29") (pin "2") (pinfunction "2_2") (pintype "passive"))
      (node (ref "J7") (pin "13") (pinfunction "13_13") (pintype "passive"))
      (node (ref "U2") (pin "21") (pinfunction "VRES_21") (pintype "output"))
    )
    (net (code "64") (name "V_OCC") (class "Default")
      (node (ref "C26") (pin "1") (pinfunction "1_1") (pintype "passive"))
      (node (ref "R19") (pin "1") (pinfunction "1_1") (pintype "passive"))
      (node (ref "R20") (pin "2") (pinfunction "2_2") (pintype "passive"))
      (node (ref "TP2") (pin "TP") (pinfunction "TP_TP") (pintype "input"))
      (node (ref "U1") (pin "4") (pinfunction "(XCK0/AIN0)PE2_4") (pintype "bidirectional"))
    )
    (net (code "65") (name "unconnected-(SW1-Pad4)") (class "Default")
      (node (ref "SW1") (pin "4") (pinfunction "4_4") (pintype "passive"))
    )
    (net (code "66") (name "unconnected-(U1-(A8)PC0-Pad35)") (class "Default")
      (node (ref "U1") (pin "35") (pinfunction "(A8)PC0_35") (pintype "bidirectional"))
    )
    (net (code "67") (name "unconnected-(U1-(A9)PC1-Pad36)") (class "Default")
      (node (ref "U1") (pin "36") (pinfunction "(A9)PC1_36") (pintype "bidirectional"))
    )
    (net (code "68") (name "unconnected-(U1-(A10)PC2-Pad37)") (class "Default")
      (node (ref "U1") (pin "37") (pinfunction "(A10)PC2_37") (pintype "bidirectional"))
    )
    (net (code "69") (name "unconnected-(U1-(A11)PC3-Pad38)") (class "Default")
      (node (ref "U1") (pin "38") (pinfunction "(A11)PC3_38") (pintype "bidirectional"))
    )
    (net (code "70") (name "unconnected-(U1-(A12)PC4-Pad39)") (class "Default")
      (node (ref "U1") (pin "39") (pinfunction "(A12)PC4_39") (pintype "bidirectional"))
    )
    (net (code "71") (name "unconnected-(U1-(A13)PC5-Pad40)") (class "Default")
      (node (ref "U1") (pin "40") (pinfunction "(A13)PC5_40") (pintype "bidirectional"))
    )
    (net (code "72") (name "unconnected-(U1-(A14)PC6-Pad41)") (class "Default")
      (node (ref "U1") (pin "41") (pinfunction "(A14)PC6_41") (pintype "bidirectional"))
    )
    (net (code "73") (name "unconnected-(U1-(AD0)PA0-Pad51)") (class "Default")
      (node (ref "U1") (pin "51") (pinfunction "(AD0)PA0_51") (pintype "bidirectional"))
    )
    (net (code "74") (name "unconnected-(U1-(AD1)PA1-Pad50)") (class "Default")
      (node (ref "U1") (pin "50") (pinfunction "(AD1)PA1_50") (pintype "bidirectional"))
    )
    (net (code "75") (name "unconnected-(U1-(AD2)PA2-Pad49)") (class "Default")
      (node (ref "U1") (pin "49") (pinfunction "(AD2)PA2_49") (pintype "bidirectional"))
    )
    (net (code "76") (name "unconnected-(U1-(AD3)PA3-Pad48)") (class "Default")
      (node (ref "U1") (pin "48") (pinfunction "(AD3)PA3_48") (pintype "bidirectional"))
    )
    (net (code "77") (name "unconnected-(U1-(AD4)PA4-Pad47)") (class "Default")
      (node (ref "U1") (pin "47") (pinfunction "(AD4)PA4_47") (pintype "bidirectional"))
    )
    (net (code "78") (name "unconnected-(U1-(AD5)PA5-Pad46)") (class "Default")
      (node (ref "U1") (pin "46") (pinfunction "(AD5)PA5_46") (pintype "bidirectional"))
    )
    (net (code "79") (name "unconnected-(U1-(AD6)PA6-Pad45)") (class "Default")
      (node (ref "U1") (pin "45") (pinfunction "(AD6)PA6_45") (pintype "bidirectional"))
    )
    (net (code "80") (name "unconnected-(U1-(AD7)PA7-Pad44)") (class "Default")
      (node (ref "U1") (pin "44") (pinfunction "(AD7)PA7_44") (pintype "bidirectional"))
    )
    (net (code "81") (name "unconnected-(U1-(ALE)PG2-Pad43)") (class "Default")
      (node (ref "U1") (pin "43") (pinfunction "(ALE)PG2_43") (pintype "bidirectional"))
    )
    (net (code "82") (name "unconnected-(U1-(OC0A{slash}OC1C)PB7-Pad17)") (class "Default")
      (node (ref "U1") (pin "17") (pinfunction "(OC0A/OC1C)PB7_17") (pintype "bidirectional"))
    )
    (net (code "83") (name "unconnected-(U1-(OC1B)PB6-Pad16)") (class "Default")
      (node (ref "U1") (pin "16") (pinfunction "(OC1B)PB6_16") (pintype "bidirectional"))
    )
    (net (code "84") (name "unconnected-(U1-(TOSC1)PG4-Pad19)") (class "Default")
      (node (ref "U1") (pin "19") (pinfunction "(TOSC1)PG4_19") (pintype "bidirectional"))
    )
    (net (code "85") (name "unconnected-(U1-(TOSC2)PG3-Pad18)") (class "Default")
      (node (ref "U1") (pin "18") (pinfunction "(TOSC2)PG3_18") (pintype "bidirectional"))
    )
    (net (code "86") (name "unconnected-(U1-(~{RD})PG1-Pad34)") (class "Default")
      (node (ref "U1") (pin "34") (pinfunction "(~{RD})PG1_34") (pintype "bidirectional"))
    )
    (net (code "87") (name "unconnected-(U1-(~{SS})PB0-Pad10)") (class "Default")
      (node (ref "U1") (pin "10") (pinfunction "(~{SS})PB0_10") (pintype "bidirectional"))
    )
    (net (code "88") (name "unconnected-(U2-RX-Pad13)") (class "Default")
      (node (ref "U2") (pin "13") (pinfunction "RX_13") (pintype "output"))
    )
    (net (code "89") (name "unconnected-(U2-SIO-Pad8)") (class "Default")
      (node (ref "U2") (pin "8") (pinfunction "SIO_8") (pintype "bidirectional"))
    )
    (net (code "90") (name "unconnected-(U2-TX-Pad9)") (class "Default")
      (node (ref "U2") (pin "9") (pinfunction "TX_9") (pintype "input"))
    )
    (net (code "91") (name "unconnected-(U3-VREF-Pad5)") (class "Default")
      (node (ref "U3") (pin "5") (pinfunction "VREF_5") (pintype "input"))
    )
  )
)
